# PS2Kbd.net
KiCad netlist of a schematic drawn in EAGLE
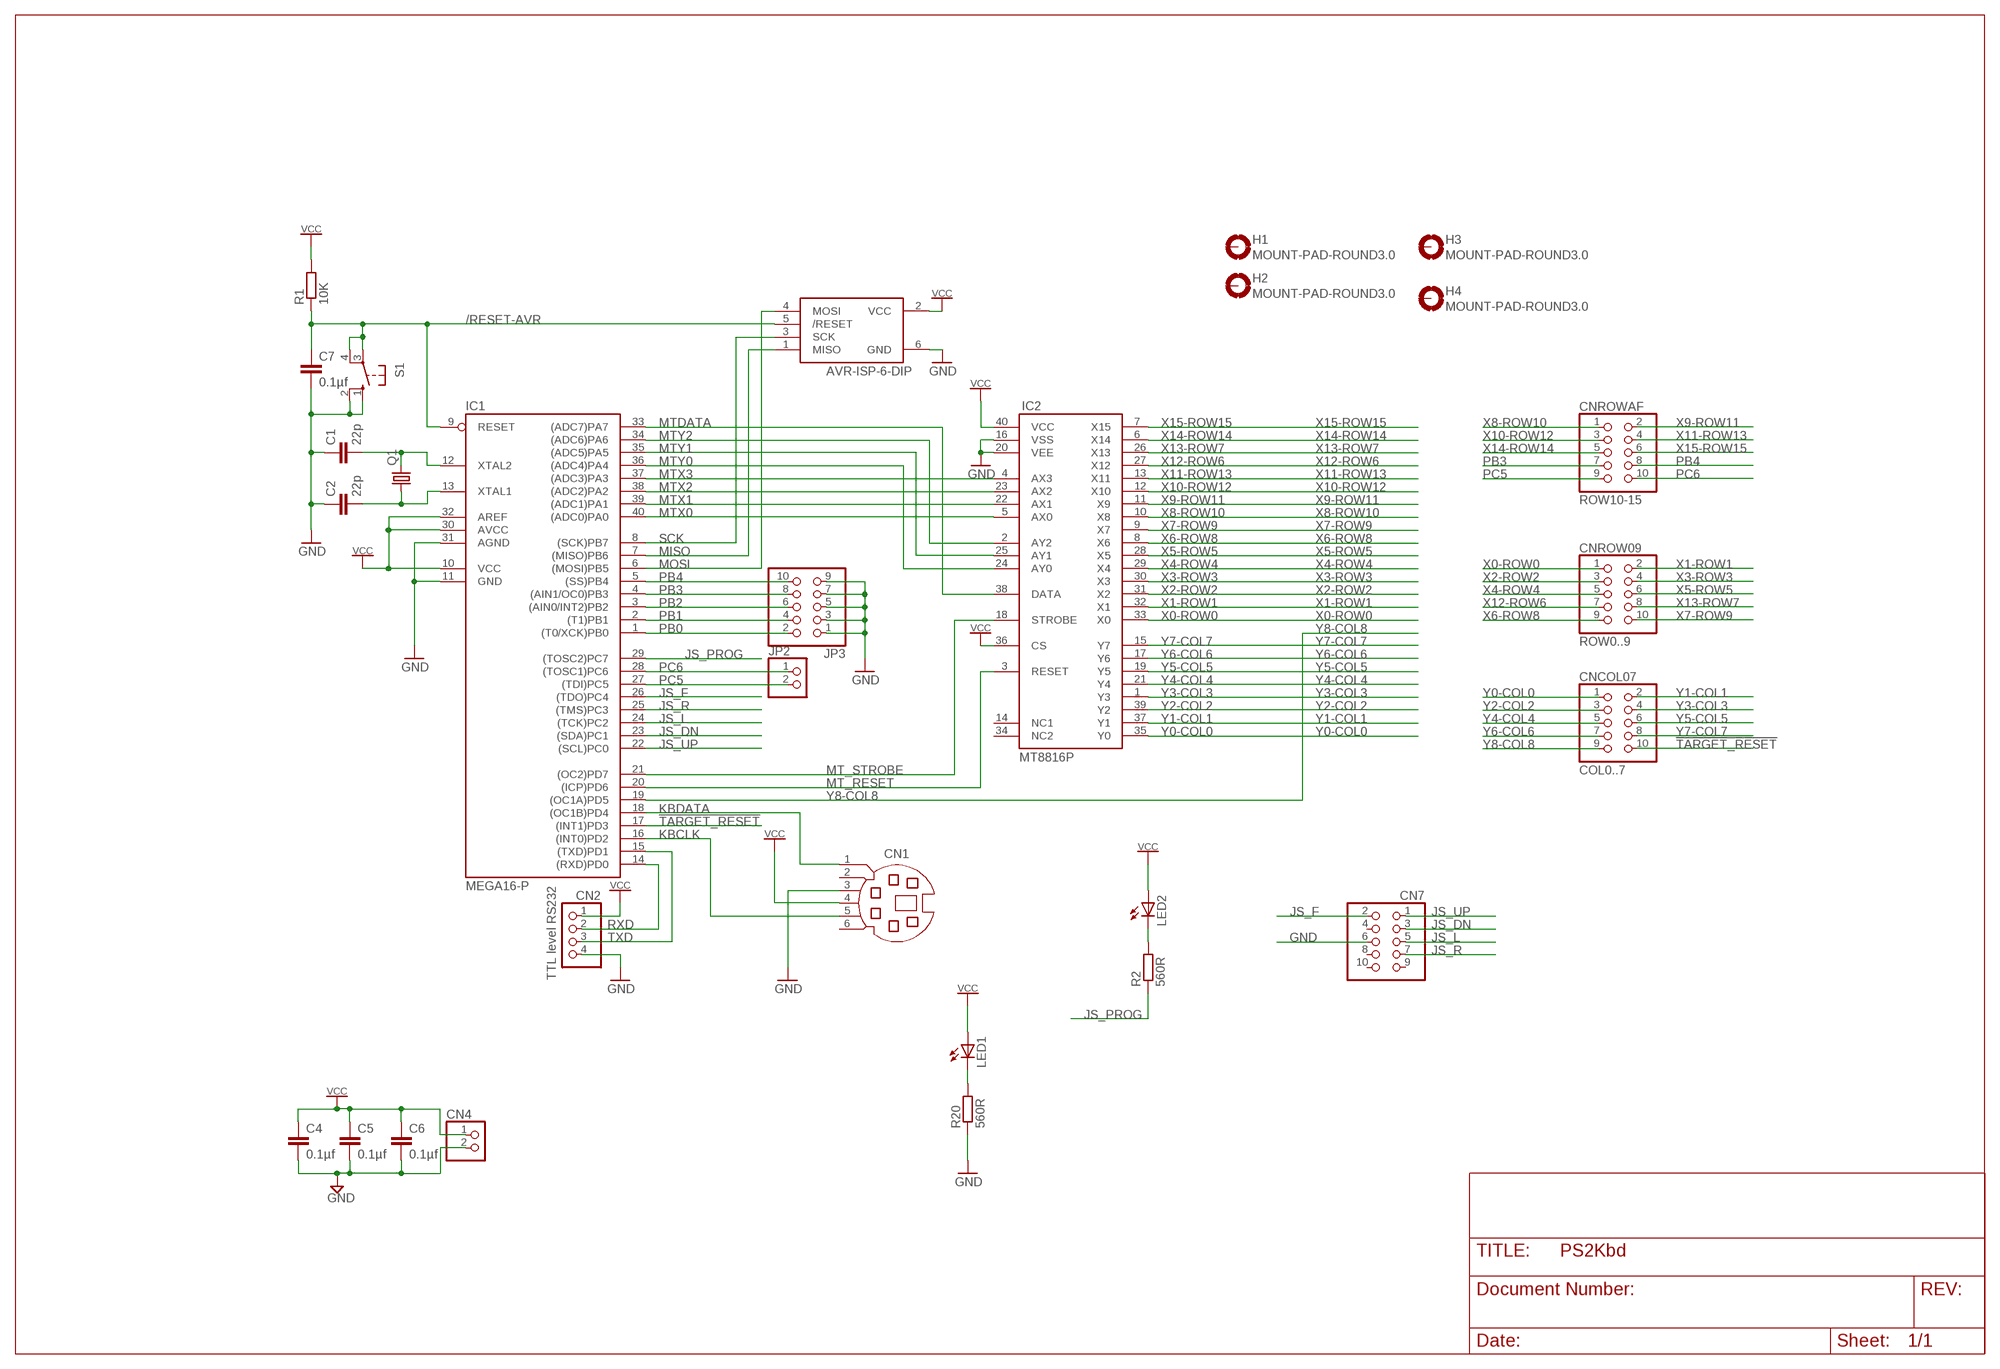
[diagram p0: schematic, sheet 1]

(export (version "E")
  (design (tool "Eeschema 10.0.6"))
  (components
    (comp (ref "C1")
      (value "22p")
      (footprint "eagle-import:C025-025X050")
      (libsource (lib "eagle-import") (part "C-EU025-025X050"))
    )
    (comp (ref "C2")
      (value "22p")
      (footprint "eagle-import:C025-025X050")
      (libsource (lib "eagle-import") (part "C-EU025-025X050"))
    )
    (comp (ref "C4")
      (value "0.1µf")
      (footprint "eagle-import:C025-025X050")
      (libsource (lib "eagle-import") (part "C-EU025-025X050"))
    )
    (comp (ref "C5")
      (value "0.1µf")
      (footprint "eagle-import:C025-025X050")
      (libsource (lib "eagle-import") (part "C-EU025-025X050"))
    )
    (comp (ref "C6")
      (value "0.1µf")
      (footprint "eagle-import:C025-025X050")
      (libsource (lib "eagle-import") (part "C-EU025-025X050"))
    )
    (comp (ref "C7")
      (value "0.1µf")
      (footprint "eagle-import:C025-025X050")
      (libsource (lib "eagle-import") (part "C-EU025-025X050"))
    )
    (comp (ref "CN1")
      (value "MD06SS")
      (footprint "eagle-import:MDIN06SS")
      (libsource (lib "eagle-import") (part "MD06SS"))
    )
    (comp (ref "CN2")
      (value "PINHD-1X4")
      (footprint "eagle-import:1X04")
      (libsource (lib "eagle-import") (part "PINHD-1X4"))
    )
    (comp (ref "CN3")
      (value "AVR-ISP-6-DIP")
      (footprint "eagle-import:2X3")
      (libsource (lib "eagle-import") (part "AVR-ISP-6-DIP"))
    )
    (comp (ref "CN4")
      (value "PINHD-1X2")
      (footprint "eagle-import:1X02")
      (libsource (lib "eagle-import") (part "PINHD-1X2"))
    )
    (comp (ref "CN7")
      (value "PINHD-2X5")
      (footprint "eagle-import:2X05")
      (libsource (lib "eagle-import") (part "PINHD-2X5"))
    )
    (comp (ref "CNCOL07")
      (value "COL0..7")
      (footprint "eagle-import:2X05")
      (libsource (lib "eagle-import") (part "PINHD-2X5"))
    )
    (comp (ref "CNROW09")
      (value "ROW0..9")
      (footprint "eagle-import:2X05")
      (libsource (lib "eagle-import") (part "PINHD-2X5"))
    )
    (comp (ref "CNROWAF")
      (value "ROW10-15")
      (footprint "eagle-import:2X05")
      (libsource (lib "eagle-import") (part "PINHD-2X5"))
    )
    (comp (ref "H1")
      (value "MOUNT-PAD-ROUND3.0")
      (footprint "eagle-import:3,0-PAD")
      (libsource (lib "eagle-import") (part "MOUNT-PAD-ROUND3.0"))
    )
    (comp (ref "H2")
      (value "MOUNT-PAD-ROUND3.0")
      (footprint "eagle-import:3,0-PAD")
      (libsource (lib "eagle-import") (part "MOUNT-PAD-ROUND3.0"))
    )
    (comp (ref "H3")
      (value "MOUNT-PAD-ROUND3.0")
      (footprint "eagle-import:3,0-PAD")
      (libsource (lib "eagle-import") (part "MOUNT-PAD-ROUND3.0"))
    )
    (comp (ref "H4")
      (value "MOUNT-PAD-ROUND3.0")
      (footprint "eagle-import:3,0-PAD")
      (libsource (lib "eagle-import") (part "MOUNT-PAD-ROUND3.0"))
    )
    (comp (ref "IC1")
      (value "MEGA16-P")
      (footprint "eagle-import:DIL40")
      (libsource (lib "eagle-import") (part "MEGA16-P"))
    )
    (comp (ref "IC2")
      (value "MT8816P")
      (footprint "eagle-import:DIL40")
      (libsource (lib "eagle-import") (part "MT8816P"))
    )
    (comp (ref "JP2")
      (value "PINHD-1X2")
      (footprint "eagle-import:1X02")
      (libsource (lib "eagle-import") (part "pinhead-round_PINHD-1X2"))
    )
    (comp (ref "JP3")
      (value "PINHD-2X5")
      (footprint "eagle-import:2X05")
      (libsource (lib "eagle-import") (part "pinhead-round_PINHD-2X5"))
    )
    (comp (ref "LED1")
      (value "LED3MM")
      (footprint "eagle-import:LED3MM")
      (libsource (lib "eagle-import") (part "LED3MM"))
    )
    (comp (ref "LED2")
      (value "LED3MM")
      (footprint "eagle-import:LED3MM")
      (libsource (lib "eagle-import") (part "LED3MM"))
    )
    (comp (ref "Q1")
      (value "CRYSTALHC49S")
      (footprint "eagle-import:HC49_S")
      (libsource (lib "eagle-import") (part "CRYSTALHC49S"))
    )
    (comp (ref "R1")
      (value "10K")
      (footprint "eagle-import:0207_10")
      (libsource (lib "eagle-import") (part "R-EU_0207/10"))
    )
    (comp (ref "R2")
      (value "560R")
      (footprint "eagle-import:0207_10")
      (libsource (lib "eagle-import") (part "R-EU_0207/10"))
    )
    (comp (ref "R20")
      (value "560R")
      (footprint "eagle-import:0207_10")
      (libsource (lib "eagle-import") (part "R-EU_0207/10"))
    )
    (comp (ref "S1")
      (value "10-XX")
      (footprint "eagle-import:B3F-10XX")
      (fields (field (name "MPN") "B3F-1000"))
      (libsource (lib "eagle-import") (part "10-XX"))
    )
  )
  (nets
    (net (code "1") (name "/JS_DN") (class "Default")
      (node (ref "CN7") (pin "3") (pinfunction "3_3") (pintype "passive"))
      (node (ref "IC1") (pin "23") (pinfunction "(SDA)PC1_23") (pintype "bidirectional"))
    )
    (net (code "2") (name "/JS_F") (class "Default")
      (node (ref "CN7") (pin "2") (pinfunction "2_2") (pintype "passive"))
      (node (ref "IC1") (pin "26") (pinfunction "(TDO)PC4_26") (pintype "bidirectional"))
    )
    (net (code "3") (name "/JS_L") (class "Default")
      (node (ref "CN7") (pin "5") (pinfunction "5_5") (pintype "passive"))
      (node (ref "IC1") (pin "24") (pinfunction "(TCK)PC2_24") (pintype "bidirectional"))
    )
    (net (code "4") (name "/JS_PROG") (class "Default")
      (node (ref "IC1") (pin "29") (pinfunction "(TOSC2)PC7_29") (pintype "bidirectional"))
      (node (ref "R2") (pin "1") (pinfunction "1_1") (pintype "passive"))
    )
    (net (code "5") (name "/JS_R") (class "Default")
      (node (ref "CN7") (pin "7") (pinfunction "7_7") (pintype "passive"))
      (node (ref "IC1") (pin "25") (pinfunction "(TMS)PC3_25") (pintype "bidirectional"))
    )
    (net (code "6") (name "/JS_UP") (class "Default")
      (node (ref "CN7") (pin "1") (pinfunction "1_1") (pintype "passive"))
      (node (ref "IC1") (pin "22") (pinfunction "(SCL)PC0_22") (pintype "bidirectional"))
    )
    (net (code "7") (name "/KBCLK") (class "Default")
      (node (ref "CN1") (pin "5") (pinfunction "5_5") (pintype "passive"))
      (node (ref "IC1") (pin "16") (pinfunction "(INT0)PD2_16") (pintype "bidirectional"))
    )
    (net (code "8") (name "/KBDATA") (class "Default")
      (node (ref "CN1") (pin "1") (pinfunction "1_1") (pintype "passive"))
      (node (ref "IC1") (pin "18") (pinfunction "(OC1B)PD4_18") (pintype "bidirectional"))
    )
    (net (code "9") (name "/MISO") (class "Default")
      (node (ref "CN3") (pin "1") (pinfunction "MISO_1") (pintype "bidirectional"))
      (node (ref "IC1") (pin "7") (pinfunction "(MISO)PB6_7") (pintype "bidirectional"))
    )
    (net (code "10") (name "/MOSI") (class "Default")
      (node (ref "CN3") (pin "4") (pinfunction "MOSI_4") (pintype "bidirectional"))
      (node (ref "IC1") (pin "6") (pinfunction "(MOSI)PB5_6") (pintype "bidirectional"))
    )
    (net (code "11") (name "/MTDATA") (class "Default")
      (node (ref "IC1") (pin "33") (pinfunction "(ADC7)PA7_33") (pintype "bidirectional"))
      (node (ref "IC2") (pin "38") (pinfunction "DATA_38") (pintype "input"))
    )
    (net (code "12") (name "/MTX0") (class "Default")
      (node (ref "IC1") (pin "40") (pinfunction "(ADC0)PA0_40") (pintype "bidirectional"))
      (node (ref "IC2") (pin "5") (pinfunction "AX0_5") (pintype "input"))
    )
    (net (code "13") (name "/MTX1") (class "Default")
      (node (ref "IC1") (pin "39") (pinfunction "(ADC1)PA1_39") (pintype "bidirectional"))
      (node (ref "IC2") (pin "22") (pinfunction "AX1_22") (pintype "input"))
    )
    (net (code "14") (name "/MTX2") (class "Default")
      (node (ref "IC1") (pin "38") (pinfunction "(ADC2)PA2_38") (pintype "bidirectional"))
      (node (ref "IC2") (pin "23") (pinfunction "AX2_23") (pintype "input"))
    )
    (net (code "15") (name "/MTX3") (class "Default")
      (node (ref "IC1") (pin "37") (pinfunction "(ADC3)PA3_37") (pintype "bidirectional"))
      (node (ref "IC2") (pin "4") (pinfunction "AX3_4") (pintype "input"))
    )
    (net (code "16") (name "/MTY0") (class "Default")
      (node (ref "IC1") (pin "36") (pinfunction "(ADC4)PA4_36") (pintype "bidirectional"))
      (node (ref "IC2") (pin "24") (pinfunction "AY0_24") (pintype "input"))
    )
    (net (code "17") (name "/MTY1") (class "Default")
      (node (ref "IC1") (pin "35") (pinfunction "(ADC5)PA5_35") (pintype "bidirectional"))
      (node (ref "IC2") (pin "25") (pinfunction "AY1_25") (pintype "input"))
    )
    (net (code "18") (name "/MTY2") (class "Default")
      (node (ref "IC1") (pin "34") (pinfunction "(ADC6)PA6_34") (pintype "bidirectional"))
      (node (ref "IC2") (pin "2") (pinfunction "AY2_2") (pintype "input"))
    )
    (net (code "19") (name "/MT_RESET") (class "Default")
      (node (ref "IC1") (pin "20") (pinfunction "(ICP)PD6_20") (pintype "bidirectional"))
      (node (ref "IC2") (pin "3") (pinfunction "RESET_3") (pintype "input"))
    )
    (net (code "20") (name "/MT_STROBE") (class "Default")
      (node (ref "IC1") (pin "21") (pinfunction "(OC2)PD7_21") (pintype "bidirectional"))
      (node (ref "IC2") (pin "18") (pinfunction "STROBE_18") (pintype "input"))
    )
    (net (code "21") (name "/PB0") (class "Default")
      (node (ref "IC1") (pin "1") (pinfunction "(T0/XCK)PB0_1") (pintype "bidirectional"))
      (node (ref "JP3") (pin "2") (pinfunction "2_2") (pintype "passive"))
    )
    (net (code "22") (name "/PB1") (class "Default")
      (node (ref "IC1") (pin "2") (pinfunction "(T1)PB1_2") (pintype "bidirectional"))
      (node (ref "JP3") (pin "4") (pinfunction "4_4") (pintype "passive"))
    )
    (net (code "23") (name "/PB2") (class "Default")
      (node (ref "IC1") (pin "3") (pinfunction "(AIN0/INT2)PB2_3") (pintype "bidirectional"))
      (node (ref "JP3") (pin "6") (pinfunction "6_6") (pintype "passive"))
    )
    (net (code "24") (name "/PB3") (class "Default")
      (node (ref "CNROWAF") (pin "7") (pinfunction "7_7") (pintype "passive"))
      (node (ref "IC1") (pin "4") (pinfunction "(AIN1/OC0)PB3_4") (pintype "bidirectional"))
      (node (ref "JP3") (pin "8") (pinfunction "8_8") (pintype "passive"))
    )
    (net (code "25") (name "/PB4") (class "Default")
      (node (ref "CNROWAF") (pin "8") (pinfunction "8_8") (pintype "passive"))
      (node (ref "IC1") (pin "5") (pinfunction "(SS)PB4_5") (pintype "bidirectional"))
      (node (ref "JP3") (pin "10") (pinfunction "10_10") (pintype "passive"))
    )
    (net (code "26") (name "/PC5") (class "Default")
      (node (ref "CNROWAF") (pin "9") (pinfunction "9_9") (pintype "passive"))
      (node (ref "IC1") (pin "27") (pinfunction "(TDI)PC5_27") (pintype "bidirectional"))
      (node (ref "JP2") (pin "2") (pinfunction "2_2") (pintype "passive"))
    )
    (net (code "27") (name "/PC6") (class "Default")
      (node (ref "CNROWAF") (pin "10") (pinfunction "10_10") (pintype "passive"))
      (node (ref "IC1") (pin "28") (pinfunction "(TOSC1)PC6_28") (pintype "bidirectional"))
      (node (ref "JP2") (pin "1") (pinfunction "1_1") (pintype "passive"))
    )
    (net (code "28") (name "/RXD") (class "Default")
      (node (ref "CN2") (pin "2") (pinfunction "2_2") (pintype "passive"))
      (node (ref "IC1") (pin "14") (pinfunction "(RXD)PD0_14") (pintype "bidirectional"))
    )
    (net (code "29") (name "/SCK") (class "Default")
      (node (ref "CN3") (pin "3") (pinfunction "SCK_3") (pintype "bidirectional"))
      (node (ref "IC1") (pin "8") (pinfunction "(SCK)PB7_8") (pintype "bidirectional"))
    )
    (net (code "30") (name "/TXD") (class "Default")
      (node (ref "CN2") (pin "3") (pinfunction "3_3") (pintype "passive"))
      (node (ref "IC1") (pin "15") (pinfunction "(TXD)PD1_15") (pintype "bidirectional"))
    )
    (net (code "31") (name "/X0-ROW0") (class "Default")
      (node (ref "CNROW09") (pin "1") (pinfunction "1_1") (pintype "passive"))
      (node (ref "IC2") (pin "33") (pinfunction "X0_33") (pintype "bidirectional"))
    )
    (net (code "32") (name "/X1-ROW1") (class "Default")
      (node (ref "CNROW09") (pin "2") (pinfunction "2_2") (pintype "passive"))
      (node (ref "IC2") (pin "32") (pinfunction "X1_32") (pintype "bidirectional"))
    )
    (net (code "33") (name "/X2-ROW2") (class "Default")
      (node (ref "CNROW09") (pin "3") (pinfunction "3_3") (pintype "passive"))
      (node (ref "IC2") (pin "31") (pinfunction "X2_31") (pintype "bidirectional"))
    )
    (net (code "34") (name "/X3-ROW3") (class "Default")
      (node (ref "CNROW09") (pin "4") (pinfunction "4_4") (pintype "passive"))
      (node (ref "IC2") (pin "30") (pinfunction "X3_30") (pintype "bidirectional"))
    )
    (net (code "35") (name "/X4-ROW4") (class "Default")
      (node (ref "CNROW09") (pin "5") (pinfunction "5_5") (pintype "passive"))
      (node (ref "IC2") (pin "29") (pinfunction "X4_29") (pintype "bidirectional"))
    )
    (net (code "36") (name "/X5-ROW5") (class "Default")
      (node (ref "CNROW09") (pin "6") (pinfunction "6_6") (pintype "passive"))
      (node (ref "IC2") (pin "28") (pinfunction "X5_28") (pintype "bidirectional"))
    )
    (net (code "37") (name "/X6-ROW8") (class "Default")
      (node (ref "CNROW09") (pin "9") (pinfunction "9_9") (pintype "passive"))
      (node (ref "IC2") (pin "8") (pinfunction "X6_8") (pintype "bidirectional"))
    )
    (net (code "38") (name "/X7-ROW9") (class "Default")
      (node (ref "CNROW09") (pin "10") (pinfunction "10_10") (pintype "passive"))
      (node (ref "IC2") (pin "9") (pinfunction "X7_9") (pintype "bidirectional"))
    )
    (net (code "39") (name "/X8-ROW10") (class "Default")
      (node (ref "CNROWAF") (pin "1") (pinfunction "1_1") (pintype "passive"))
      (node (ref "IC2") (pin "10") (pinfunction "X8_10") (pintype "bidirectional"))
    )
    (net (code "40") (name "/X9-ROW11") (class "Default")
      (node (ref "CNROWAF") (pin "2") (pinfunction "2_2") (pintype "passive"))
      (node (ref "IC2") (pin "11") (pinfunction "X9_11") (pintype "bidirectional"))
    )
    (net (code "41") (name "/X10-ROW12") (class "Default")
      (node (ref "CNROWAF") (pin "3") (pinfunction "3_3") (pintype "passive"))
      (node (ref "IC2") (pin "12") (pinfunction "X10_12") (pintype "bidirectional"))
    )
    (net (code "42") (name "/X11-ROW13") (class "Default")
      (node (ref "CNROWAF") (pin "4") (pinfunction "4_4") (pintype "passive"))
      (node (ref "IC2") (pin "13") (pinfunction "X11_13") (pintype "bidirectional"))
    )
    (net (code "43") (name "/X12-ROW6") (class "Default")
      (node (ref "CNROW09") (pin "7") (pinfunction "7_7") (pintype "passive"))
      (node (ref "IC2") (pin "27") (pinfunction "X12_27") (pintype "bidirectional"))
    )
    (net (code "44") (name "/X13-ROW7") (class "Default")
      (node (ref "CNROW09") (pin "8") (pinfunction "8_8") (pintype "passive"))
      (node (ref "IC2") (pin "26") (pinfunction "X13_26") (pintype "bidirectional"))
    )
    (net (code "45") (name "/X14-ROW14") (class "Default")
      (node (ref "CNROWAF") (pin "5") (pinfunction "5_5") (pintype "passive"))
      (node (ref "IC2") (pin "6") (pinfunction "X14_6") (pintype "bidirectional"))
    )
    (net (code "46") (name "/X15-ROW15") (class "Default")
      (node (ref "CNROWAF") (pin "6") (pinfunction "6_6") (pintype "passive"))
      (node (ref "IC2") (pin "7") (pinfunction "X15_7") (pintype "bidirectional"))
    )
    (net (code "47") (name "/Y0-COL0") (class "Default")
      (node (ref "CNCOL07") (pin "1") (pinfunction "1_1") (pintype "passive"))
      (node (ref "IC2") (pin "35") (pinfunction "Y0_35") (pintype "bidirectional"))
    )
    (net (code "48") (name "/Y1-COL1") (class "Default")
      (node (ref "CNCOL07") (pin "2") (pinfunction "2_2") (pintype "passive"))
      (node (ref "IC2") (pin "37") (pinfunction "Y1_37") (pintype "bidirectional"))
    )
    (net (code "49") (name "/Y2-COL2") (class "Default")
      (node (ref "CNCOL07") (pin "3") (pinfunction "3_3") (pintype "passive"))
      (node (ref "IC2") (pin "39") (pinfunction "Y2_39") (pintype "bidirectional"))
    )
    (net (code "50") (name "/Y3-COL3") (class "Default")
      (node (ref "CNCOL07") (pin "4") (pinfunction "4_4") (pintype "passive"))
      (node (ref "IC2") (pin "1") (pinfunction "Y3_1") (pintype "bidirectional"))
    )
    (net (code "51") (name "/Y4-COL4") (class "Default")
      (node (ref "CNCOL07") (pin "5") (pinfunction "5_5") (pintype "passive"))
      (node (ref "IC2") (pin "21") (pinfunction "Y4_21") (pintype "bidirectional"))
    )
    (net (code "52") (name "/Y5-COL5") (class "Default")
      (node (ref "CNCOL07") (pin "6") (pinfunction "6_6") (pintype "passive"))
      (node (ref "IC2") (pin "19") (pinfunction "Y5_19") (pintype "bidirectional"))
    )
    (net (code "53") (name "/Y6-COL6") (class "Default")
      (node (ref "CNCOL07") (pin "7") (pinfunction "7_7") (pintype "passive"))
      (node (ref "IC2") (pin "17") (pinfunction "Y6_17") (pintype "bidirectional"))
    )
    (net (code "54") (name "/Y7-COL7") (class "Default")
      (node (ref "CNCOL07") (pin "8") (pinfunction "8_8") (pintype "passive"))
      (node (ref "IC2") (pin "15") (pinfunction "Y7_15") (pintype "bidirectional"))
    )
    (net (code "55") (name "/Y8-COL8") (class "Default")
      (node (ref "CNCOL07") (pin "9") (pinfunction "9_9") (pintype "passive"))
      (node (ref "IC1") (pin "19") (pinfunction "(OC1A)PD5_19") (pintype "bidirectional"))
    )
    (net (code "56") (name "/{slash}RESET-AVR") (class "Default")
      (node (ref "C7") (pin "1") (pinfunction "1_1") (pintype "passive"))
      (node (ref "CN3") (pin "5") (pinfunction "/RESET_5") (pintype "bidirectional"))
      (node (ref "IC1") (pin "9") (pinfunction "RESET_9") (pintype "input"))
      (node (ref "R1") (pin "1") (pinfunction "1_1") (pintype "passive"))
      (node (ref "S1") (pin "3") (pinfunction "P_3") (pintype "passive"))
      (node (ref "S1") (pin "4") (pinfunction "P1_4") (pintype "passive"))
    )
    (net (code "57") (name "/~{TARGET_RESET}") (class "Default")
      (node (ref "CNCOL07") (pin "10") (pinfunction "10_10") (pintype "passive"))
      (node (ref "IC1") (pin "17") (pinfunction "(INT1)PD3_17") (pintype "bidirectional"))
    )
    (net (code "58") (name "GND") (class "Default")
      (node (ref "C1") (pin "1") (pinfunction "1_1") (pintype "passive"))
      (node (ref "C2") (pin "1") (pinfunction "1_1") (pintype "passive"))
      (node (ref "C4") (pin "2") (pinfunction "2_2") (pintype "passive"))
      (node (ref "C5") (pin "2") (pinfunction "2_2") (pintype "passive"))
      (node (ref "C6") (pin "2") (pinfunction "2_2") (pintype "passive"))
      (node (ref "C7") (pin "2") (pinfunction "2_2") (pintype "passive"))
      (node (ref "CN1") (pin "3") (pinfunction "3_3") (pintype "passive"))
      (node (ref "CN2") (pin "4") (pinfunction "4_4") (pintype "passive"))
      (node (ref "CN3") (pin "6") (pinfunction "GND_6") (pintype "power_in"))
      (node (ref "CN4") (pin "2") (pinfunction "2_2") (pintype "passive"))
      (node (ref "CN7") (pin "6") (pinfunction "6_6") (pintype "passive"))
      (node (ref "IC1") (pin "11") (pinfunction "GND_11") (pintype "power_in"))
      (node (ref "IC1") (pin "31") (pinfunction "AGND_31") (pintype "power_in"))
      (node (ref "IC2") (pin "16") (pinfunction "VSS_16") (pintype "power_in"))
      (node (ref "IC2") (pin "20") (pinfunction "VEE_20") (pintype "power_in"))
      (node (ref "JP3") (pin "1") (pinfunction "1_1") (pintype "passive"))
      (node (ref "JP3") (pin "3") (pinfunction "3_3") (pintype "passive"))
      (node (ref "JP3") (pin "5") (pinfunction "5_5") (pintype "passive"))
      (node (ref "JP3") (pin "7") (pinfunction "7_7") (pintype "passive"))
      (node (ref "JP3") (pin "9") (pinfunction "9_9") (pintype "passive"))
      (node (ref "R20") (pin "1") (pinfunction "1_1") (pintype "passive"))
      (node (ref "S1") (pin "1") (pinfunction "S_1") (pintype "passive"))
      (node (ref "S1") (pin "2") (pinfunction "S1_2") (pintype "passive"))
    )
    (net (code "59") (name "Net-(IC1-XTAL1)") (class "Default")
      (node (ref "C2") (pin "2") (pinfunction "2_2") (pintype "passive"))
      (node (ref "IC1") (pin "13") (pinfunction "XTAL1_13") (pintype "bidirectional"))
      (node (ref "Q1") (pin "1") (pinfunction "1_1") (pintype "passive"))
    )
    (net (code "60") (name "Net-(IC1-XTAL2)") (class "Default")
      (node (ref "C1") (pin "2") (pinfunction "2_2") (pintype "passive"))
      (node (ref "IC1") (pin "12") (pinfunction "XTAL2_12") (pintype "bidirectional"))
      (node (ref "Q1") (pin "2") (pinfunction "2_2") (pintype "passive"))
    )
    (net (code "61") (name "Net-(LED1-C)") (class "Default")
      (node (ref "LED1") (pin "K") (pinfunction "C_K") (pintype "passive"))
      (node (ref "R20") (pin "2") (pinfunction "2_2") (pintype "passive"))
    )
    (net (code "62") (name "Net-(LED2-C)") (class "Default")
      (node (ref "LED2") (pin "K") (pinfunction "C_K") (pintype "passive"))
      (node (ref "R2") (pin "2") (pinfunction "2_2") (pintype "passive"))
    )
    (net (code "63") (name "VCC") (class "Default")
      (node (ref "C4") (pin "1") (pinfunction "1_1") (pintype "passive"))
      (node (ref "C5") (pin "1") (pinfunction "1_1") (pintype "passive"))
      (node (ref "C6") (pin "1") (pinfunction "1_1") (pintype "passive"))
      (node (ref "CN1") (pin "4") (pinfunction "4_4") (pintype "passive"))
      (node (ref "CN2") (pin "1") (pinfunction "1_1") (pintype "passive"))
      (node (ref "CN3") (pin "2") (pinfunction "VCC_2") (pintype "power_in"))
      (node (ref "CN4") (pin "1") (pinfunction "1_1") (pintype "passive"))
      (node (ref "IC1") (pin "10") (pinfunction "VCC_10") (pintype "power_in"))
      (node (ref "IC1") (pin "30") (pinfunction "AVCC_30") (pintype "power_in"))
      (node (ref "IC1") (pin "32") (pinfunction "AREF_32") (pintype "power_in"))
      (node (ref "IC2") (pin "36") (pinfunction "CS_36") (pintype "input"))
      (node (ref "IC2") (pin "40") (pinfunction "VCC_40") (pintype "power_in"))
      (node (ref "LED1") (pin "A") (pinfunction "A_A") (pintype "passive"))
      (node (ref "LED2") (pin "A") (pinfunction "A_A") (pintype "passive"))
      (node (ref "R1") (pin "2") (pinfunction "2_2") (pintype "passive"))
    )
    (net (code "64") (name "unconnected-(CN1-Pad2)") (class "Default")
      (node (ref "CN1") (pin "2") (pinfunction "2_2") (pintype "passive"))
    )
    (net (code "65") (name "unconnected-(CN1-Pad6)") (class "Default")
      (node (ref "CN1") (pin "6") (pinfunction "6_6") (pintype "passive"))
    )
    (net (code "66") (name "unconnected-(CN7-Pad4)") (class "Default")
      (node (ref "CN7") (pin "4") (pinfunction "4_4") (pintype "passive"))
    )
    (net (code "67") (name "unconnected-(CN7-Pad8)") (class "Default")
      (node (ref "CN7") (pin "8") (pinfunction "8_8") (pintype "passive"))
    )
    (net (code "68") (name "unconnected-(CN7-Pad9)") (class "Default")
      (node (ref "CN7") (pin "9") (pinfunction "9_9") (pintype "passive"))
    )
    (net (code "69") (name "unconnected-(CN7-Pad10)") (class "Default")
      (node (ref "CN7") (pin "10") (pinfunction "10_10") (pintype "passive"))
    )
    (net (code "70") (name "unconnected-(H1-MOUNT-PadB3,0)") (class "Default")
      (node (ref "H1") (pin "B3,0") (pinfunction "MOUNT_B3,0") (pintype "passive"))
    )
    (net (code "71") (name "unconnected-(H2-MOUNT-PadB3,0)") (class "Default")
      (node (ref "H2") (pin "B3,0") (pinfunction "MOUNT_B3,0") (pintype "passive"))
    )
    (net (code "72") (name "unconnected-(H3-MOUNT-PadB3,0)") (class "Default")
      (node (ref "H3") (pin "B3,0") (pinfunction "MOUNT_B3,0") (pintype "passive"))
    )
    (net (code "73") (name "unconnected-(H4-MOUNT-PadB3,0)") (class "Default")
      (node (ref "H4") (pin "B3,0") (pinfunction "MOUNT_B3,0") (pintype "passive"))
    )
    (net (code "74") (name "unconnected-(IC2-NC1-Pad14)") (class "Default")
      (node (ref "IC2") (pin "14") (pinfunction "NC1_14") (pintype "no_connect"))
    )
    (net (code "75") (name "unconnected-(IC2-NC2-Pad34)") (class "Default")
      (node (ref "IC2") (pin "34") (pinfunction "NC2_34") (pintype "no_connect"))
    )
  )
)
